# RTDIface.net
KiCad netlist of a schematic drawn in Altium Designer
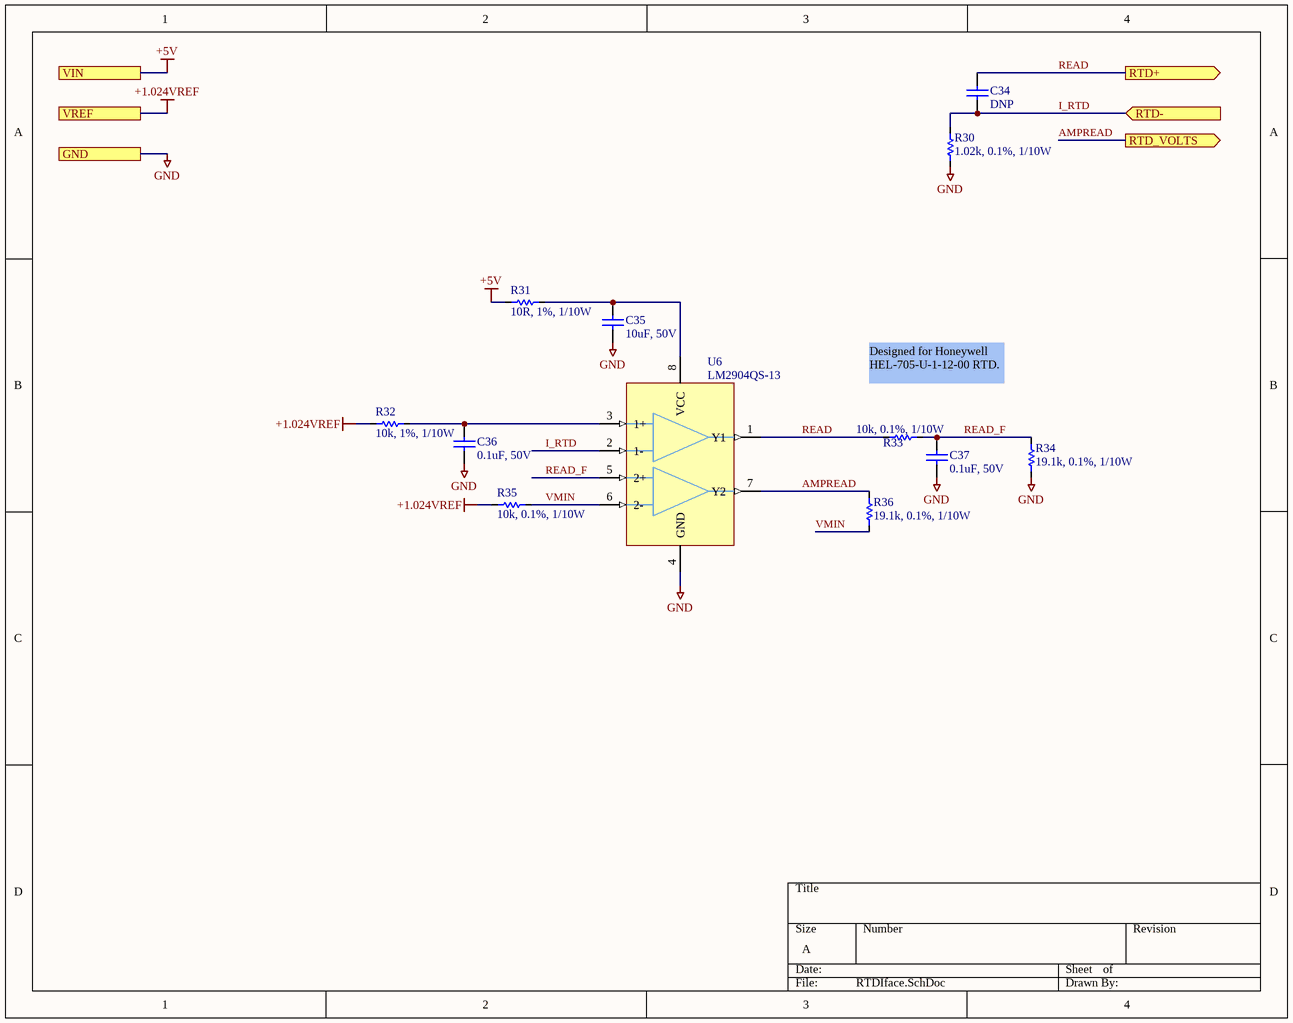
[diagram p0: RTDIface.SchDoc]

(export (version "E")
  (design (tool "Eeschema 10.0.6"))
  (components
    (comp (ref "C34")
      (value "DNP")
      (footprint "0603")
      (description "CAP CER 10000PF 100V C0G 0603")
      (fields (field (name "PART NUMBER") "NS00848"))
      (libsource (lib "FullPartsDB") (part "Cap"))
    )
    (comp (ref "C35")
      (value "10uF, 50V")
      (footprint "1206")
      (description "CAP CER 10UF 50V X7R 1206")
      (fields (field (name "PART NUMBER") "NS00832"))
      (libsource (lib "FullPartsDB") (part "Cap"))
    )
    (comp (ref "C36")
      (value "0.1uF, 50V")
      (footprint "0805")
      (description "0.10µF ±10% 50V Ceramic Capacitor X7R 0805 (2012 Metric)")
      (fields (field (name "PART NUMBER") "NS00353"))
      (libsource (lib "FullPartsDB") (part "Cap"))
    )
    (comp (ref "C37")
      (value "0.1uF, 50V")
      (footprint "0805")
      (description "0.10µF ±10% 50V Ceramic Capacitor X7R 0805 (2012 Metric)")
      (fields (field (name "PART NUMBER") "NS00353"))
      (libsource (lib "FullPartsDB") (part "Cap"))
    )
    (comp (ref "R30")
      (value "1.02k, 0.1%, 1/10W")
      (footprint "0603")
      (description "RES SMD 1.02KOHM 0.1% 1/10W 0603")
      (fields (field (name "PART NUMBER") "NS00884"))
      (libsource (lib "FullPartsDB") (part "RESISTOR"))
    )
    (comp (ref "R31")
      (value "10R, 1%, 1/10W")
      (footprint "0603")
      (description "RES 10 OHM 1% 1/10W 0603")
      (fields (field (name "PART NUMBER") "NS00796"))
      (libsource (lib "FullPartsDB") (part "RESISTOR"))
    )
    (comp (ref "R32")
      (value "10k, 1%, 1/10W")
      (footprint "0603")
      (description "RES 10K OHM 1% 1/10W 0603")
      (fields (field (name "PART NUMBER") "NS00820"))
      (libsource (lib "FullPartsDB") (part "RESISTOR"))
    )
    (comp (ref "R33")
      (value "10k, 0.1%, 1/10W")
      (footprint "0603")
      (description "RES SMD 10K OHM 0.1% 1/10W 0603")
      (fields (field (name "PART NUMBER") "NS00885"))
      (libsource (lib "FullPartsDB") (part "RESISTOR"))
    )
    (comp (ref "R34")
      (value "19.1k, 0.1%, 1/10W")
      (footprint "0603")
      (description "RES SMD 19.1KOHM 0.1% 1/10W 0603")
      (fields (field (name "PART NUMBER") "NS00886"))
      (libsource (lib "FullPartsDB") (part "RESISTOR"))
    )
    (comp (ref "R35")
      (value "10k, 0.1%, 1/10W")
      (footprint "0603")
      (description "RES SMD 10K OHM 0.1% 1/10W 0603")
      (fields (field (name "PART NUMBER") "NS00885"))
      (libsource (lib "FullPartsDB") (part "RESISTOR"))
    )
    (comp (ref "R36")
      (value "19.1k, 0.1%, 1/10W")
      (footprint "0603")
      (description "RES SMD 19.1KOHM 0.1% 1/10W 0603")
      (fields (field (name "PART NUMBER") "NS00886"))
      (libsource (lib "FullPartsDB") (part "RESISTOR"))
    )
    (comp (ref "U6")
      (value "LM2904QS-13")
      (footprint "SOIC127P600X163-8N")
      (description "IC OPAMP GP 2 CIRCUIT 8SO")
      (fields (field (name "PART NUMBER") "NS00864"))
      (libsource (lib "FullPartsDB") (part "AMP_DUAL"))
    )
  )
  (nets
    (net (code "1") (name "+1.024VREF") (class "Default")
      (node (ref "R32") (pin "2") (pinfunction "2_2") (pintype "passive"))
      (node (ref "R35") (pin "1") (pinfunction "1_1") (pintype "passive"))
    )
    (net (code "2") (name "+5V") (class "Default")
      (node (ref "R31") (pin "1") (pinfunction "1_1") (pintype "passive"))
    )
    (net (code "3") (name "/AMPREAD") (class "Default")
      (node (ref "R36") (pin "2") (pinfunction "2_2") (pintype "passive"))
      (node (ref "U6") (pin "7") (pinfunction "Y2_7") (pintype "output"))
    )
    (net (code "4") (name "/I_RTD") (class "Default")
      (node (ref "C34") (pin "2") (pinfunction "2_2") (pintype "passive"))
      (node (ref "R30") (pin "2") (pinfunction "2_2") (pintype "passive"))
      (node (ref "U6") (pin "2") (pinfunction "1-_2") (pintype "input"))
    )
    (net (code "5") (name "/READ") (class "Default")
      (node (ref "C34") (pin "1") (pinfunction "1_1") (pintype "passive"))
      (node (ref "R33") (pin "1") (pinfunction "1_1") (pintype "passive"))
      (node (ref "U6") (pin "1") (pinfunction "Y1_1") (pintype "output"))
    )
    (net (code "6") (name "/READ_F") (class "Default")
      (node (ref "C37") (pin "2") (pinfunction "2_2") (pintype "passive"))
      (node (ref "R33") (pin "2") (pinfunction "2_2") (pintype "passive"))
      (node (ref "R34") (pin "2") (pinfunction "2_2") (pintype "passive"))
      (node (ref "U6") (pin "5") (pinfunction "2+_5") (pintype "input"))
    )
    (net (code "7") (name "/VMIN") (class "Default")
      (node (ref "R35") (pin "2") (pinfunction "2_2") (pintype "passive"))
      (node (ref "R36") (pin "1") (pinfunction "1_1") (pintype "passive"))
      (node (ref "U6") (pin "6") (pinfunction "2-_6") (pintype "input"))
    )
    (net (code "8") (name "GND") (class "Default")
      (node (ref "C35") (pin "1") (pinfunction "1_1") (pintype "passive"))
      (node (ref "C36") (pin "1") (pinfunction "1_1") (pintype "passive"))
      (node (ref "C37") (pin "1") (pinfunction "1_1") (pintype "passive"))
      (node (ref "R30") (pin "1") (pinfunction "1_1") (pintype "passive"))
      (node (ref "R34") (pin "1") (pinfunction "1_1") (pintype "passive"))
      (node (ref "U6") (pin "4") (pinfunction "GND_4") (pintype "power_in"))
    )
    (net (code "9") (name "Net-(U6-1+)") (class "Default")
      (node (ref "C36") (pin "2") (pinfunction "2_2") (pintype "passive"))
      (node (ref "R32") (pin "1") (pinfunction "1_1") (pintype "passive"))
      (node (ref "U6") (pin "3") (pinfunction "1+_3") (pintype "input"))
    )
    (net (code "10") (name "Net-(U6-VCC)") (class "Default")
      (node (ref "C35") (pin "2") (pinfunction "2_2") (pintype "passive"))
      (node (ref "R31") (pin "2") (pinfunction "2_2") (pintype "passive"))
      (node (ref "U6") (pin "8") (pinfunction "VCC_8") (pintype "power_in"))
    )
  )
)
